# Power.net
KiCad netlist of a schematic drawn in Altium Designer
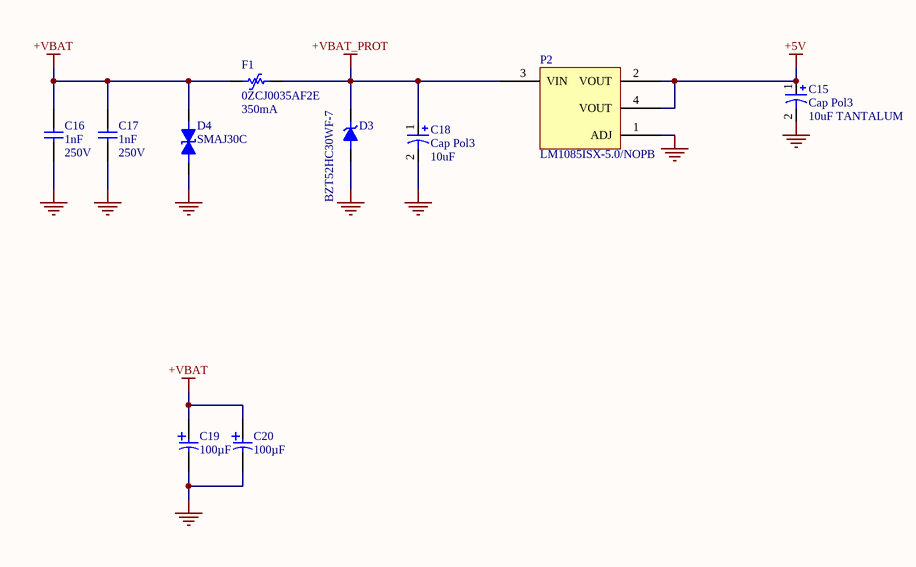
[diagram p0: Power.SchDoc]

(export (version "E")
  (design (tool "Eeschema 10.0.6"))
  (components
    (comp (ref "C15")
      (value "Cap Pol3")
      (footprint "1206-Polarized")
      (description "Polarized Capacitor (Surface Mount)")
      (fields (field (name "ALTIUM_VALUE") "10uF TANTALUM") (field (name "PUBLISHER") "Altium Limited"))
      (libsource (lib "Miscellaneous Devices") (part "Cap Pol3"))
    )
    (comp (ref "C16")
      (value "1nF")
      (footprint "1206")
      (fields
        (field (name "PART NUMBER") "CC0805KRX7RYBB102")
        (field (name "TOLERANCE") "±10%")
        (field (name "VOLTAGE") "250V")
        (field (name "MANUFACTURER") "Yageo")
      )
      (libsource (lib "Capacitors") (part "Capacitor"))
    )
    (comp (ref "C17")
      (value "1nF")
      (footprint "1206")
      (fields
        (field (name "PART NUMBER") "CC0805KRX7RYBB102")
        (field (name "TOLERANCE") "±10%")
        (field (name "VOLTAGE") "250V")
        (field (name "MANUFACTURER") "Yageo")
      )
      (libsource (lib "Capacitors") (part "Capacitor"))
    )
    (comp (ref "C18")
      (value "Cap Pol3")
      (footprint "1206-Polarized")
      (description "Polarized Capacitor (Surface Mount)")
      (fields (field (name "ALTIUM_VALUE") "10uF") (field (name "PUBLISHER") "Altium Limited"))
      (libsource (lib "Miscellaneous Devices") (part "Cap Pol3"))
    )
    (comp (ref "C19")
      (value "100µF")
      (footprint "CAPAE7066X80M")
      (fields (field (name "Comment") "EEE-FK1V101XP"))
      (libsource (lib "PDUv2") (part "EEE-FK1V101XP"))
    )
    (comp (ref "C20")
      (value "100µF")
      (footprint "CAPAE7066X80M")
      (fields (field (name "Comment") "EEE-FK1V101XP"))
      (libsource (lib "PDUv2") (part "EEE-FK1V101XP"))
    )
    (comp (ref "D3")
      (value "BZT52HC30WF-7")
      (footprint "SODFL340X115-2N")
      (libsource (lib "PDUv2") (part "BZT52HC30WF-7"))
    )
    (comp (ref "D4")
      (value "SMAJ30C")
      (footprint "SON127P500X135-2N")
      (libsource (lib "PDU-UV17") (part "SMAJ30C"))
    )
    (comp (ref "F1")
      (value "0ZCJ0035AF2E")
      (footprint "0ZCJ-1206-0.9")
      (fields (field (name "ALTIUM_VALUE") "350mA"))
      (libsource (lib "PDU-UV17") (part "0ZCJ0035AF2E"))
    )
    (comp (ref "P2")
      (value "LM1085ISX-5.0/NOPB")
      (footprint "TO-263")
      (libsource (lib "CANDAQ") (part "LM1085ISX-5.0/NOPB"))
    )
  )
  (nets
    (net (code "1") (name "+5V") (class "Default")
      (node (ref "C15") (pin "1") (pinfunction "1_1") (pintype "passive"))
      (node (ref "P2") (pin "2") (pinfunction "VOUT_2") (pintype "passive"))
      (node (ref "P2") (pin "4") (pinfunction "VOUT_4") (pintype "passive"))
    )
    (net (code "2") (name "+VBAT") (class "Default")
      (node (ref "C16") (pin "1") (pinfunction "1_1") (pintype "passive"))
      (node (ref "C17") (pin "1") (pinfunction "1_1") (pintype "passive"))
      (node (ref "C19") (pin "2") (pinfunction "2_2") (pintype "passive"))
      (node (ref "C20") (pin "2") (pinfunction "2_2") (pintype "passive"))
      (node (ref "D4") (pin "1") (pinfunction "1_1") (pintype "passive"))
      (node (ref "F1") (pin "1") (pinfunction "1_1") (pintype "passive"))
    )
    (net (code "3") (name "+VBAT_PROT") (class "Default")
      (node (ref "C18") (pin "1") (pinfunction "1_1") (pintype "passive"))
      (node (ref "D3") (pin "1") (pinfunction "K_1") (pintype "passive"))
      (node (ref "F1") (pin "2") (pinfunction "2_2") (pintype "passive"))
      (node (ref "P2") (pin "3") (pinfunction "VIN_3") (pintype "passive"))
    )
    (net (code "4") (name "GND") (class "Default")
      (node (ref "C15") (pin "2") (pinfunction "2_2") (pintype "passive"))
      (node (ref "C16") (pin "2") (pinfunction "2_2") (pintype "passive"))
      (node (ref "C17") (pin "2") (pinfunction "2_2") (pintype "passive"))
      (node (ref "C18") (pin "2") (pinfunction "2_2") (pintype "passive"))
      (node (ref "C19") (pin "1") (pinfunction "1_1") (pintype "passive"))
      (node (ref "C20") (pin "1") (pinfunction "1_1") (pintype "passive"))
      (node (ref "D3") (pin "2") (pinfunction "A_2") (pintype "passive"))
      (node (ref "D4") (pin "2") (pinfunction "2_2") (pintype "passive"))
      (node (ref "P2") (pin "1") (pinfunction "ADJ_1") (pintype "passive"))
    )
  )
)
